# SCH.net
KiCad netlist of a schematic drawn in Altium Designer
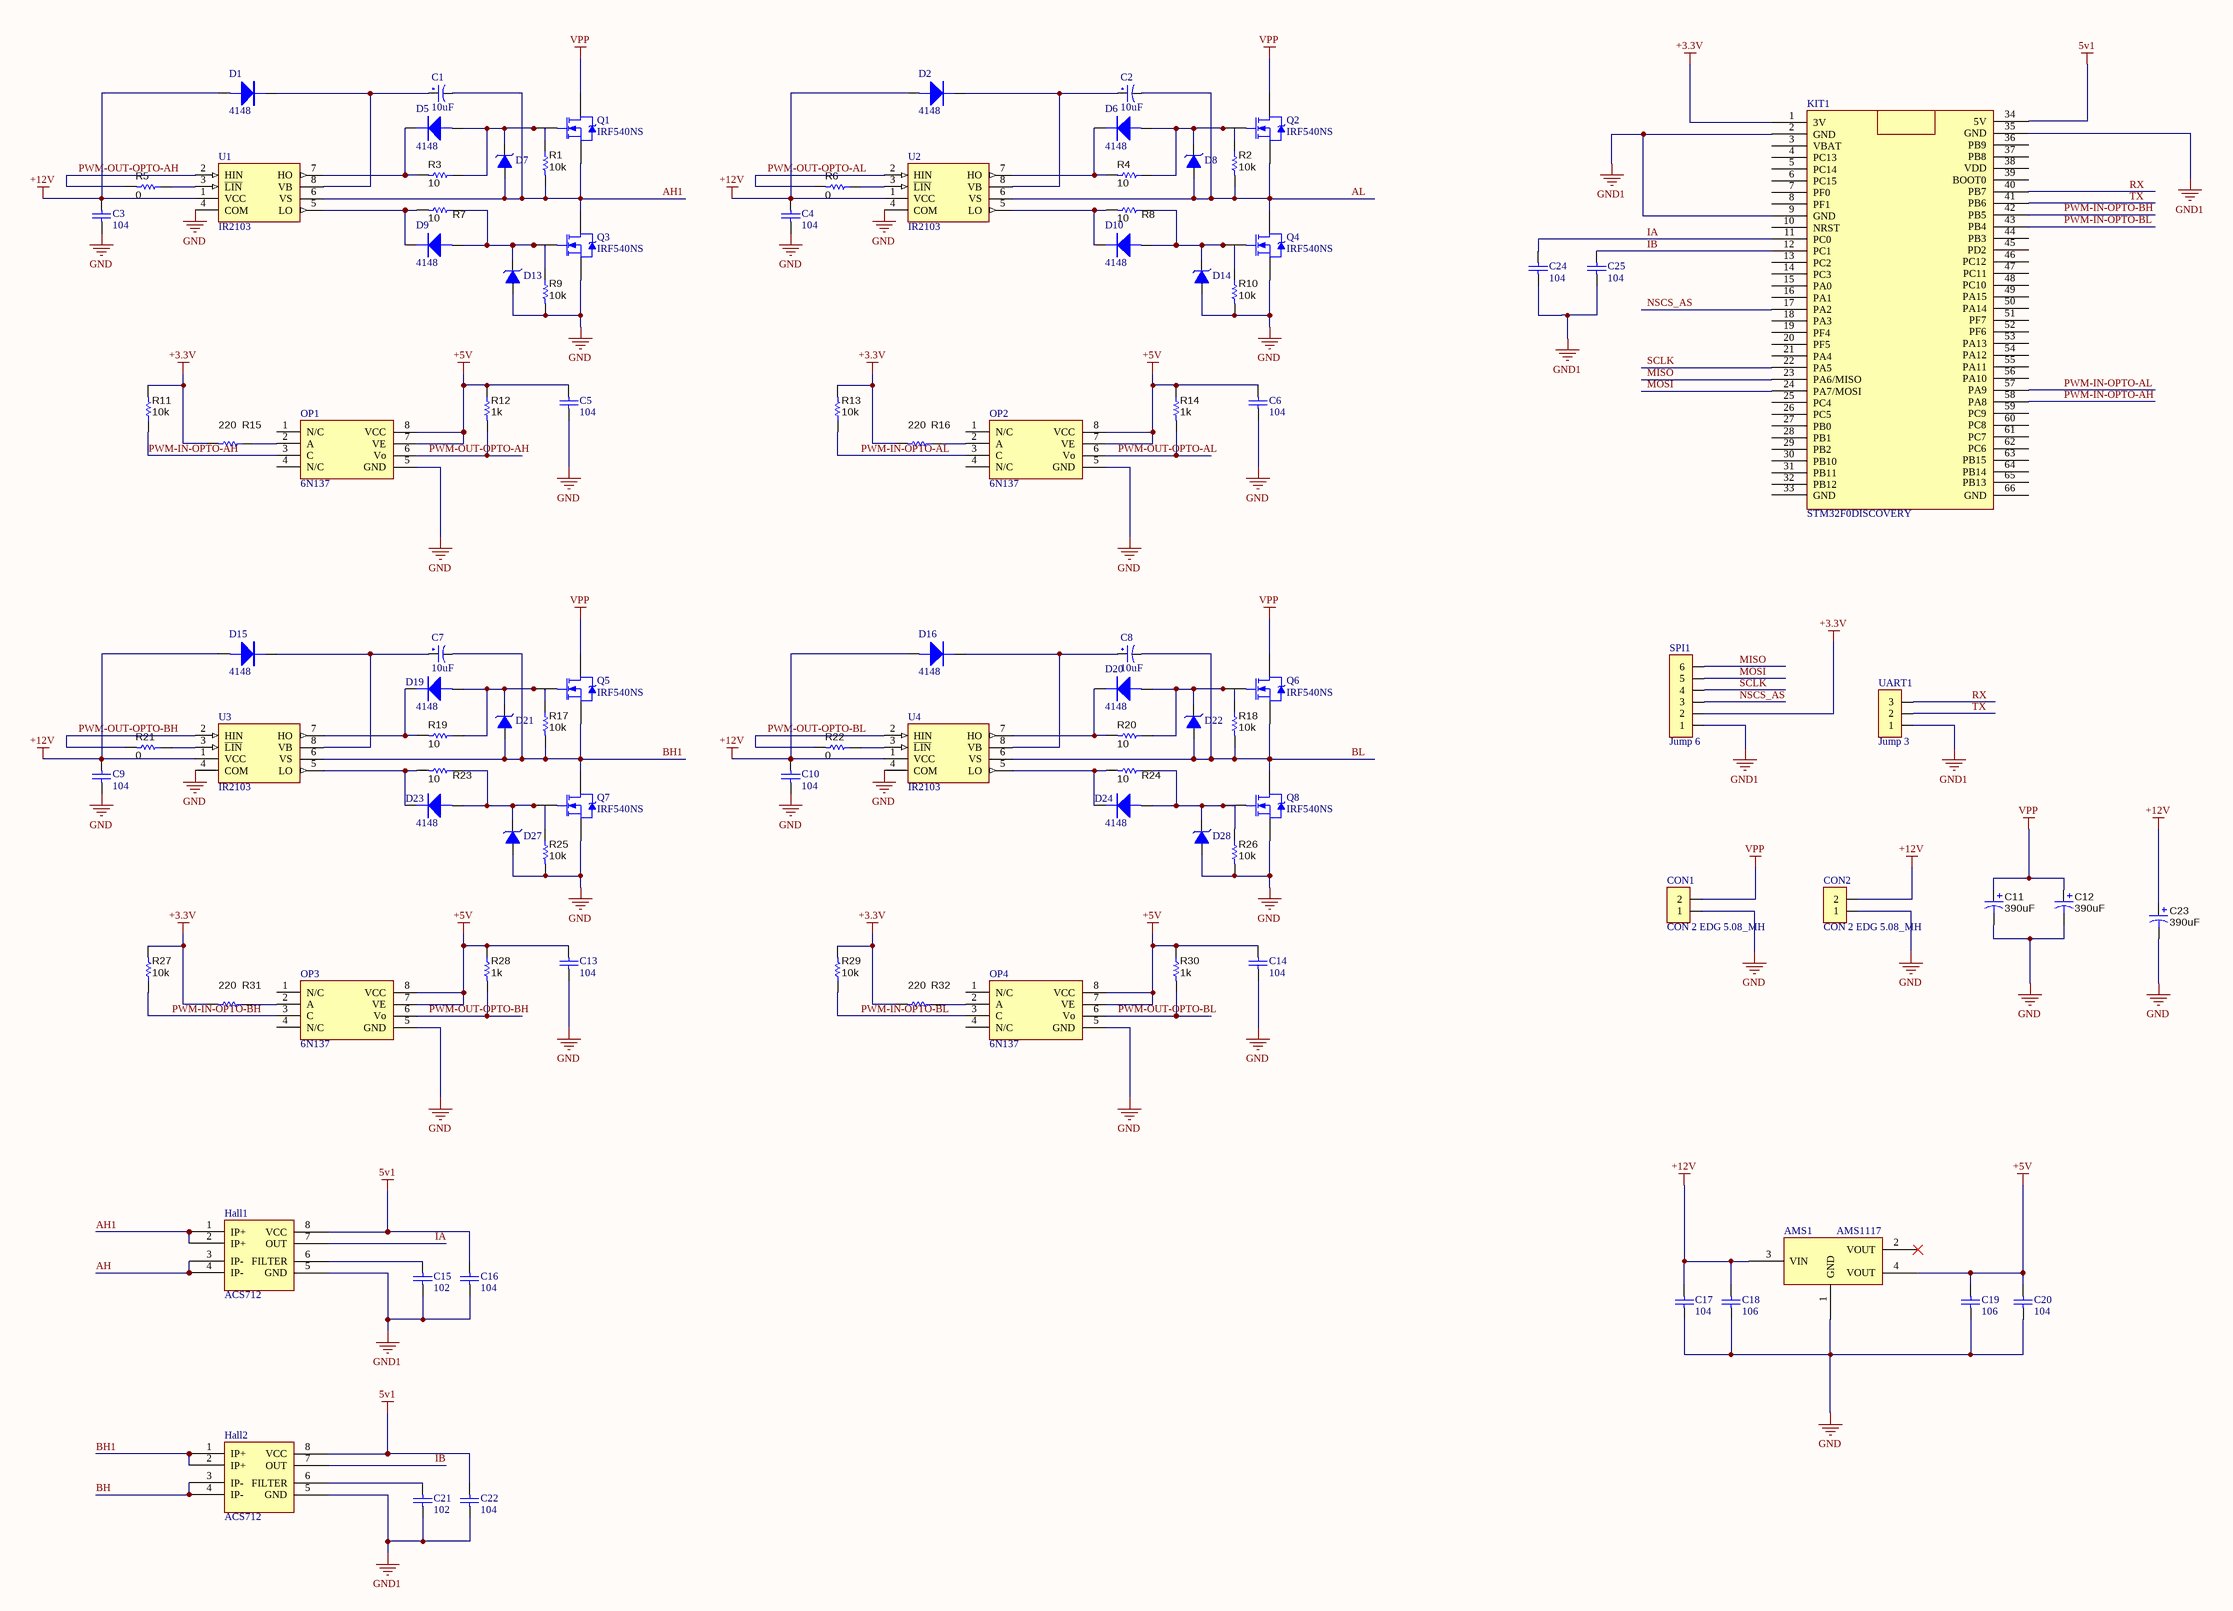
[diagram p0: SCH.SchDoc]

(export (version "E")
  (design (tool "Eeschema 10.0.6"))
  (components
    (comp (ref "AMS1")
      (value "AMS1117")
      (footprint "SOT223")
      (libsource (lib "mySch") (part "AMS1117-3.3V SOT223"))
    )
    (comp (ref "C1")
      (value "10uF")
      (footprint "CP1/2")
      (description "Cap P  0,1uF < 22uF , 16 - 50V")
      (libsource (lib "MH_DA_THU_VIEN_16122016") (part "TU_HOA_4.7uF_50V_MH"))
    )
    (comp (ref "C2")
      (value "10uF")
      (footprint "CP1/2")
      (description "Cap P  0,1uF < 22uF , 16 - 50V")
      (libsource (lib "MH_DA_THU_VIEN_16122016") (part "TU_HOA_4.7uF_50V_MH"))
    )
    (comp (ref "C3")
      (value "104")
      (footprint "TU_SMD_0805")
      (description "Ceramic Chip Capacitor - Standard")
      (fields (field (name "PUBLISHER") "Altium Limited"))
      (libsource (lib "mySch") (part "Capacitor 0805"))
    )
    (comp (ref "C4")
      (value "104")
      (footprint "TU_SMD_0805")
      (description "Ceramic Chip Capacitor - Standard")
      (fields (field (name "PUBLISHER") "Altium Limited"))
      (libsource (lib "mySch") (part "Capacitor 0805"))
    )
    (comp (ref "C5")
      (value "104")
      (footprint "TU_SMD_0805")
      (description "Ceramic Chip Capacitor - Standard")
      (fields (field (name "PUBLISHER") "Altium Limited"))
      (libsource (lib "mySch") (part "Capacitor 0805"))
    )
    (comp (ref "C6")
      (value "104")
      (footprint "TU_SMD_0805")
      (description "Ceramic Chip Capacitor - Standard")
      (fields (field (name "PUBLISHER") "Altium Limited"))
      (libsource (lib "mySch") (part "Capacitor 0805"))
    )
    (comp (ref "C7")
      (value "10uF")
      (footprint "CP1/2")
      (description "Cap P  0,1uF < 22uF , 16 - 50V")
      (libsource (lib "MH_DA_THU_VIEN_16122016") (part "TU_HOA_4.7uF_50V_MH"))
    )
    (comp (ref "C8")
      (value "10uF")
      (footprint "CP1/2")
      (description "Cap P  0,1uF < 22uF , 16 - 50V")
      (libsource (lib "MH_DA_THU_VIEN_16122016") (part "TU_HOA_4.7uF_50V_MH"))
    )
    (comp (ref "C9")
      (value "104")
      (footprint "TU_SMD_0805")
      (description "Ceramic Chip Capacitor - Standard")
      (fields (field (name "PUBLISHER") "Altium Limited"))
      (libsource (lib "mySch") (part "Capacitor 0805"))
    )
    (comp (ref "C10")
      (value "104")
      (footprint "TU_SMD_0805")
      (description "Ceramic Chip Capacitor - Standard")
      (fields (field (name "PUBLISHER") "Altium Limited"))
      (libsource (lib "mySch") (part "Capacitor 0805"))
    )
    (comp (ref "C11")
      (value "390uF")
      (footprint "CAP_12.5 X 25")
      (description "CAP ALUM 390UF 20% 50V RADIAL")
      (fields
        (field (name "PARTNUMBER") "UHW1H391MPD6")
        (field (name "MANUFACTURER") "Nichicon")
        (field (name "VALUEDISPLAYED") "390uF")
        (field (name "PUBLISHER") "Texas Instruments")
      )
      (libsource (lib "mySch") (part "Capacitor TuHoa"))
    )
    (comp (ref "C12")
      (value "390uF")
      (footprint "CAP_12.5 X 25")
      (description "CAP ALUM 390UF 20% 50V RADIAL")
      (fields
        (field (name "PARTNUMBER") "UHW1H391MPD6")
        (field (name "MANUFACTURER") "Nichicon")
        (field (name "VALUEDISPLAYED") "390uF")
        (field (name "PUBLISHER") "Texas Instruments")
      )
      (libsource (lib "mySch") (part "Capacitor TuHoa"))
    )
    (comp (ref "C13")
      (value "104")
      (footprint "TU_SMD_0805")
      (description "Ceramic Chip Capacitor - Standard")
      (fields (field (name "PUBLISHER") "Altium Limited"))
      (libsource (lib "mySch") (part "Capacitor 0805"))
    )
    (comp (ref "C14")
      (value "104")
      (footprint "TU_SMD_0805")
      (description "Ceramic Chip Capacitor - Standard")
      (fields (field (name "PUBLISHER") "Altium Limited"))
      (libsource (lib "mySch") (part "Capacitor 0805"))
    )
    (comp (ref "C15")
      (value "102")
      (footprint "TU_SMD_0805")
      (description "Ceramic Chip Capacitor - Standard")
      (fields (field (name "PUBLISHER") "Altium Limited"))
      (libsource (lib "mySch") (part "Capacitor 0805"))
    )
    (comp (ref "C16")
      (value "104")
      (footprint "TU_SMD_0805")
      (description "Ceramic Chip Capacitor - Standard")
      (fields (field (name "PUBLISHER") "Altium Limited"))
      (libsource (lib "mySch") (part "Capacitor 0805"))
    )
    (comp (ref "C17")
      (value "104")
      (footprint "TU_SMD_0805")
      (description "Ceramic Chip Capacitor - Standard")
      (fields (field (name "PUBLISHER") "Altium Limited"))
      (libsource (lib "mySch") (part "Capacitor 0805"))
    )
    (comp (ref "C18")
      (value "106")
      (footprint "TU_SMD_0805")
      (description "Ceramic Chip Capacitor - Standard")
      (fields (field (name "PUBLISHER") "Altium Limited"))
      (libsource (lib "mySch") (part "Capacitor 0805"))
    )
    (comp (ref "C19")
      (value "106")
      (footprint "TU_SMD_0805")
      (description "Ceramic Chip Capacitor - Standard")
      (fields (field (name "PUBLISHER") "Altium Limited"))
      (libsource (lib "mySch") (part "Capacitor 0805"))
    )
    (comp (ref "C20")
      (value "104")
      (footprint "TU_SMD_0805")
      (description "Ceramic Chip Capacitor - Standard")
      (fields (field (name "PUBLISHER") "Altium Limited"))
      (libsource (lib "mySch") (part "Capacitor 0805"))
    )
    (comp (ref "C21")
      (value "102")
      (footprint "TU_SMD_0805")
      (description "Ceramic Chip Capacitor - Standard")
      (fields (field (name "PUBLISHER") "Altium Limited"))
      (libsource (lib "mySch") (part "Capacitor 0805"))
    )
    (comp (ref "C22")
      (value "104")
      (footprint "TU_SMD_0805")
      (description "Ceramic Chip Capacitor - Standard")
      (fields (field (name "PUBLISHER") "Altium Limited"))
      (libsource (lib "mySch") (part "Capacitor 0805"))
    )
    (comp (ref "C23")
      (value "390uF")
      (footprint "CP1/3.0")
      (fields
        (field (name "PARTNUMBER") "UHW1H391MPD6")
        (field (name "MANUFACTURER") "Nichicon")
        (field (name "VALUEDISPLAYED") "390uF")
        (field (name "PUBLISHER") "Texas Instruments")
      )
      (libsource (lib "mySch") (part "Capacitor TuHoa"))
    )
    (comp (ref "C24")
      (value "104")
      (footprint "TU_SMD_0805")
      (description "Ceramic Chip Capacitor - Standard")
      (fields (field (name "PUBLISHER") "Altium Limited"))
      (libsource (lib "mySch") (part "Capacitor 0805"))
    )
    (comp (ref "C25")
      (value "104")
      (footprint "TU_SMD_0805")
      (description "Ceramic Chip Capacitor - Standard")
      (fields (field (name "PUBLISHER") "Altium Limited"))
      (libsource (lib "mySch") (part "Capacitor 0805"))
    )
    (comp (ref "CON1")
      (value "CON 2 EDG 5.08_MH")
      (footprint "CON 2 EDG 5.08")
      (description "CON 2 EDG 5.08 (xanh cong)")
      (libsource (lib "mySch") (part "CON 2 EDG 5.08_MH"))
    )
    (comp (ref "CON2")
      (value "CON 2 EDG 5.08_MH")
      (footprint "CON 2 EDG 5.08")
      (description "CON 2 EDG 5.08 (xanh cong)")
      (libsource (lib "mySch") (part "CON 2 EDG 5.08_MH"))
    )
    (comp (ref "D1")
      (value "4148")
      (footprint "Diode Zener 1N5363B 5W 30V")
      (description "Diode 1N4148 DO35 450mA 100V ( 1N4148 DIP)")
      (libsource (lib "MH_DA_THU_VIEN_16122016") (part "Diode 1N4148 DO35 450mA 100V ( 1N4148 DIP)_MH"))
    )
    (comp (ref "D2")
      (value "4148")
      (footprint "Diode Zener 1N5363B 5W 30V")
      (description "Diode 1N4148 DO35 450mA 100V ( 1N4148 DIP)")
      (libsource (lib "MH_DA_THU_VIEN_16122016") (part "Diode 1N4148 DO35 450mA 100V ( 1N4148 DIP)_MH"))
    )
    (comp (ref "D5")
      (value "4148")
      (footprint "Diode Zener 1N5363B 5W 30V")
      (description "Diode 1N4148 DO35 450mA 100V ( 1N4148 DIP)")
      (libsource (lib "MH_DA_THU_VIEN_16122016") (part "Diode 1N4148 DO35 450mA 100V ( 1N4148 DIP)_MH"))
    )
    (comp (ref "D6")
      (value "4148")
      (footprint "Diode Zener 1N5363B 5W 30V")
      (description "Diode 1N4148 DO35 450mA 100V ( 1N4148 DIP)")
      (libsource (lib "MH_DA_THU_VIEN_16122016") (part "Diode 1N4148 DO35 450mA 100V ( 1N4148 DIP)_MH"))
    )
    (comp (ref "D7") (value "~") (footprint "DO-35") (libsource (lib "mySch") (part "Diode Zener")))
    (comp (ref "D8") (value "~") (footprint "DO-35") (libsource (lib "mySch") (part "Diode Zener")))
    (comp (ref "D9")
      (value "4148")
      (footprint "Diode Zener 1N5363B 5W 30V")
      (description "Diode 1N4148 DO35 450mA 100V ( 1N4148 DIP)")
      (libsource (lib "MH_DA_THU_VIEN_16122016") (part "Diode 1N4148 DO35 450mA 100V ( 1N4148 DIP)_MH"))
    )
    (comp (ref "D10")
      (value "4148")
      (footprint "Diode Zener 1N5363B 5W 30V")
      (description "Diode 1N4148 DO35 450mA 100V ( 1N4148 DIP)")
      (libsource (lib "MH_DA_THU_VIEN_16122016") (part "Diode 1N4148 DO35 450mA 100V ( 1N4148 DIP)_MH"))
    )
    (comp (ref "D13") (value "~") (footprint "DO-35") (libsource (lib "mySch") (part "Diode Zener")))
    (comp (ref "D14") (value "~") (footprint "DO-35") (libsource (lib "mySch") (part "Diode Zener")))
    (comp (ref "D15")
      (value "4148")
      (footprint "Diode Zener 1N5363B 5W 30V")
      (description "Diode 1N4148 DO35 450mA 100V ( 1N4148 DIP)")
      (libsource (lib "MH_DA_THU_VIEN_16122016") (part "Diode 1N4148 DO35 450mA 100V ( 1N4148 DIP)_MH"))
    )
    (comp (ref "D16")
      (value "4148")
      (footprint "Diode Zener 1N5363B 5W 30V")
      (description "Diode 1N4148 DO35 450mA 100V ( 1N4148 DIP)")
      (libsource (lib "MH_DA_THU_VIEN_16122016") (part "Diode 1N4148 DO35 450mA 100V ( 1N4148 DIP)_MH"))
    )
    (comp (ref "D19")
      (value "4148")
      (footprint "Diode Zener 1N5363B 5W 30V")
      (description "Diode 1N4148 DO35 450mA 100V ( 1N4148 DIP)")
      (libsource (lib "MH_DA_THU_VIEN_16122016") (part "Diode 1N4148 DO35 450mA 100V ( 1N4148 DIP)_MH"))
    )
    (comp (ref "D20")
      (value "4148")
      (footprint "Diode Zener 1N5363B 5W 30V")
      (description "Diode 1N4148 DO35 450mA 100V ( 1N4148 DIP)")
      (libsource (lib "MH_DA_THU_VIEN_16122016") (part "Diode 1N4148 DO35 450mA 100V ( 1N4148 DIP)_MH"))
    )
    (comp (ref "D21") (value "~") (footprint "DO-35") (libsource (lib "mySch") (part "Diode Zener")))
    (comp (ref "D22") (value "~") (footprint "DO-35") (libsource (lib "mySch") (part "Diode Zener")))
    (comp (ref "D23")
      (value "4148")
      (footprint "Diode Zener 1N5363B 5W 30V")
      (description "Diode 1N4148 DO35 450mA 100V ( 1N4148 DIP)")
      (libsource (lib "MH_DA_THU_VIEN_16122016") (part "Diode 1N4148 DO35 450mA 100V ( 1N4148 DIP)_MH"))
    )
    (comp (ref "D24")
      (value "4148")
      (footprint "Diode Zener 1N5363B 5W 30V")
      (description "Diode 1N4148 DO35 450mA 100V ( 1N4148 DIP)")
      (libsource (lib "MH_DA_THU_VIEN_16122016") (part "Diode 1N4148 DO35 450mA 100V ( 1N4148 DIP)_MH"))
    )
    (comp (ref "D27") (value "~") (footprint "DO-35") (libsource (lib "mySch") (part "Diode Zener")))
    (comp (ref "D28") (value "~") (footprint "DO-35") (libsource (lib "mySch") (part "Diode Zener")))
    (comp (ref "Hall1") (value "ACS712") (footprint "SOP 8") (libsource (lib "mySch") (part "ACS712")))
    (comp (ref "Hall2") (value "ACS712") (footprint "SOP 8") (libsource (lib "mySch") (part "ACS712")))
    (comp (ref "KIT1")
      (value "STM32F0DISCOVERY")
      (footprint "STM32F0DISCOVERY-6N137")
      (libsource (lib "mySch") (part "STM32F0DISCOVERY"))
    )
    (comp (ref "OP1")
      (value "6N137 DIP8 Opto 10Mbit")
      (footprint "DIP8")
      (description "6N137 DIP8 Opto 10Mbit/s")
      (libsource (lib "mySch") (part "6N137"))
    )
    (comp (ref "OP2")
      (value "6N137 DIP8 Opto 10Mbit")
      (footprint "DIP8")
      (description "6N137 DIP8 Opto 10Mbit/s")
      (libsource (lib "mySch") (part "6N137"))
    )
    (comp (ref "OP3")
      (value "6N137 DIP8 Opto 10Mbit")
      (footprint "DIP8")
      (description "6N137 DIP8 Opto 10Mbit/s")
      (libsource (lib "mySch") (part "6N137"))
    )
    (comp (ref "OP4")
      (value "6N137 DIP8 Opto 10Mbit")
      (footprint "DIP8")
      (description "6N137 DIP8 Opto 10Mbit/s")
      (libsource (lib "mySch") (part "6N137"))
    )
    (comp (ref "Q1")
      (value "IRF540NS")
      (footprint "D2PAK_M_1")
      (description "HEXFET Power MOSFET")
      (fields (field (name "PUBLISHER") "Altium Limited"))
      (libsource (lib "mySch") (part "IRF540NS"))
    )
    (comp (ref "Q2")
      (value "IRF540NS")
      (footprint "D2PAK_M_1")
      (description "HEXFET Power MOSFET")
      (fields (field (name "PUBLISHER") "Altium Limited"))
      (libsource (lib "mySch") (part "IRF540NS"))
    )
    (comp (ref "Q3")
      (value "IRF540NS")
      (footprint "D2PAK_M_1")
      (description "HEXFET Power MOSFET")
      (fields (field (name "PUBLISHER") "Altium Limited"))
      (libsource (lib "mySch") (part "IRF540NS"))
    )
    (comp (ref "Q4")
      (value "IRF540NS")
      (footprint "D2PAK_M_1")
      (description "HEXFET Power MOSFET")
      (fields (field (name "PUBLISHER") "Altium Limited"))
      (libsource (lib "mySch") (part "IRF540NS"))
    )
    (comp (ref "Q5")
      (value "IRF540NS")
      (footprint "D2PAK_M_1")
      (description "HEXFET Power MOSFET")
      (fields (field (name "PUBLISHER") "Altium Limited"))
      (libsource (lib "mySch") (part "IRF540NS"))
    )
    (comp (ref "Q6")
      (value "IRF540NS")
      (footprint "D2PAK_M_1")
      (description "HEXFET Power MOSFET")
      (fields (field (name "PUBLISHER") "Altium Limited"))
      (libsource (lib "mySch") (part "IRF540NS"))
    )
    (comp (ref "Q7")
      (value "IRF540NS")
      (footprint "D2PAK_M_1")
      (description "HEXFET Power MOSFET")
      (fields (field (name "PUBLISHER") "Altium Limited"))
      (libsource (lib "mySch") (part "IRF540NS"))
    )
    (comp (ref "Q8")
      (value "IRF540NS")
      (footprint "D2PAK_M_1")
      (description "HEXFET Power MOSFET")
      (fields (field (name "PUBLISHER") "Altium Limited"))
      (libsource (lib "mySch") (part "IRF540NS"))
    )
    (comp (ref "R1")
      (value "10k")
      (footprint "Tro SMD 0805")
      (description "RES, 100, 1%, 0.1 W, 0402")
      (fields
        (field (name "PARTNUMBER") "ERJ-2RKF1000X")
        (field (name "MANUFACTURER") "Panasonic")
        (field (name "PUBLISHER") "Texas Instruments")
      )
      (libsource (lib "mySch") (part "R nho"))
    )
    (comp (ref "R2")
      (value "10k")
      (footprint "Tro SMD 0805")
      (description "RES, 100, 1%, 0.1 W, 0402")
      (fields
        (field (name "PARTNUMBER") "ERJ-2RKF1000X")
        (field (name "MANUFACTURER") "Panasonic")
        (field (name "PUBLISHER") "Texas Instruments")
      )
      (libsource (lib "mySch") (part "R nho"))
    )
    (comp (ref "R3")
      (value "10")
      (footprint "Tro SMD 0805")
      (description "RES, 100, 1%, 0.1 W, 0402")
      (fields
        (field (name "PARTNUMBER") "ERJ-2RKF1000X")
        (field (name "MANUFACTURER") "Panasonic")
        (field (name "PUBLISHER") "Texas Instruments")
      )
      (libsource (lib "mySch") (part "R nho"))
    )
    (comp (ref "R4")
      (value "10")
      (footprint "Tro SMD 0805")
      (description "RES, 100, 1%, 0.1 W, 0402")
      (fields
        (field (name "PARTNUMBER") "ERJ-2RKF1000X")
        (field (name "MANUFACTURER") "Panasonic")
        (field (name "PUBLISHER") "Texas Instruments")
      )
      (libsource (lib "mySch") (part "R nho"))
    )
    (comp (ref "R5")
      (value "0")
      (footprint "Tro SMD 0805")
      (description "RES, 100, 1%, 0.1 W, 0402")
      (fields
        (field (name "PARTNUMBER") "ERJ-2RKF1000X")
        (field (name "MANUFACTURER") "Panasonic")
        (field (name "PUBLISHER") "Texas Instruments")
      )
      (libsource (lib "mySch") (part "R nho"))
    )
    (comp (ref "R6")
      (value "0")
      (footprint "Tro SMD 0805")
      (description "RES, 100, 1%, 0.1 W, 0402")
      (fields
        (field (name "PARTNUMBER") "ERJ-2RKF1000X")
        (field (name "MANUFACTURER") "Panasonic")
        (field (name "PUBLISHER") "Texas Instruments")
      )
      (libsource (lib "mySch") (part "R nho"))
    )
    (comp (ref "R7")
      (value "10")
      (footprint "Tro SMD 0805")
      (description "RES, 100, 1%, 0.1 W, 0402")
      (fields
        (field (name "PARTNUMBER") "ERJ-2RKF1000X")
        (field (name "MANUFACTURER") "Panasonic")
        (field (name "PUBLISHER") "Texas Instruments")
      )
      (libsource (lib "mySch") (part "R nho"))
    )
    (comp (ref "R8")
      (value "10")
      (footprint "Tro SMD 0805")
      (description "RES, 100, 1%, 0.1 W, 0402")
      (fields
        (field (name "PARTNUMBER") "ERJ-2RKF1000X")
        (field (name "MANUFACTURER") "Panasonic")
        (field (name "PUBLISHER") "Texas Instruments")
      )
      (libsource (lib "mySch") (part "R nho"))
    )
    (comp (ref "R9")
      (value "10k")
      (footprint "Tro SMD 0805")
      (description "RES, 100, 1%, 0.1 W, 0402")
      (fields
        (field (name "PARTNUMBER") "ERJ-2RKF1000X")
        (field (name "MANUFACTURER") "Panasonic")
        (field (name "PUBLISHER") "Texas Instruments")
      )
      (libsource (lib "mySch") (part "R nho"))
    )
    (comp (ref "R10")
      (value "10k")
      (footprint "Tro SMD 0805")
      (description "RES, 100, 1%, 0.1 W, 0402")
      (fields
        (field (name "PARTNUMBER") "ERJ-2RKF1000X")
        (field (name "MANUFACTURER") "Panasonic")
        (field (name "PUBLISHER") "Texas Instruments")
      )
      (libsource (lib "mySch") (part "R nho"))
    )
    (comp (ref "R11")
      (value "10k")
      (footprint "Tro SMD 0805")
      (description "RES, 100, 1%, 0.1 W, 0402")
      (fields
        (field (name "PARTNUMBER") "ERJ-2RKF1000X")
        (field (name "MANUFACTURER") "Panasonic")
        (field (name "PUBLISHER") "Texas Instruments")
      )
      (libsource (lib "mySch") (part "R nho"))
    )
    (comp (ref "R12")
      (value "1k")
      (footprint "Tro SMD 0805")
      (description "RES, 100, 1%, 0.1 W, 0402")
      (fields
        (field (name "PARTNUMBER") "ERJ-2RKF1000X")
        (field (name "MANUFACTURER") "Panasonic")
        (field (name "PUBLISHER") "Texas Instruments")
      )
      (libsource (lib "mySch") (part "R nho"))
    )
    (comp (ref "R13")
      (value "10k")
      (footprint "Tro SMD 0805")
      (description "RES, 100, 1%, 0.1 W, 0402")
      (fields
        (field (name "PARTNUMBER") "ERJ-2RKF1000X")
        (field (name "MANUFACTURER") "Panasonic")
        (field (name "PUBLISHER") "Texas Instruments")
      )
      (libsource (lib "mySch") (part "R nho"))
    )
    (comp (ref "R14")
      (value "1k")
      (footprint "Tro SMD 0805")
      (description "RES, 100, 1%, 0.1 W, 0402")
      (fields
        (field (name "PARTNUMBER") "ERJ-2RKF1000X")
        (field (name "MANUFACTURER") "Panasonic")
        (field (name "PUBLISHER") "Texas Instruments")
      )
      (libsource (lib "mySch") (part "R nho"))
    )
    (comp (ref "R15")
      (value "220")
      (footprint "Tro SMD 0805")
      (description "RES, 100, 1%, 0.1 W, 0402")
      (fields
        (field (name "PARTNUMBER") "ERJ-2RKF1000X")
        (field (name "MANUFACTURER") "Panasonic")
        (field (name "PUBLISHER") "Texas Instruments")
      )
      (libsource (lib "mySch") (part "R nho"))
    )
    (comp (ref "R16")
      (value "220")
      (footprint "Tro SMD 0805")
      (description "RES, 100, 1%, 0.1 W, 0402")
      (fields
        (field (name "PARTNUMBER") "ERJ-2RKF1000X")
        (field (name "MANUFACTURER") "Panasonic")
        (field (name "PUBLISHER") "Texas Instruments")
      )
      (libsource (lib "mySch") (part "R nho"))
    )
    (comp (ref "R17")
      (value "10k")
      (footprint "Tro SMD 0805")
      (description "RES, 100, 1%, 0.1 W, 0402")
      (fields
        (field (name "PARTNUMBER") "ERJ-2RKF1000X")
        (field (name "MANUFACTURER") "Panasonic")
        (field (name "PUBLISHER") "Texas Instruments")
      )
      (libsource (lib "mySch") (part "R nho"))
    )
    (comp (ref "R18")
      (value "10k")
      (footprint "Tro SMD 0805")
      (description "RES, 100, 1%, 0.1 W, 0402")
      (fields
        (field (name "PARTNUMBER") "ERJ-2RKF1000X")
        (field (name "MANUFACTURER") "Panasonic")
        (field (name "PUBLISHER") "Texas Instruments")
      )
      (libsource (lib "mySch") (part "R nho"))
    )
    (comp (ref "R19")
      (value "10")
      (footprint "Tro SMD 0805")
      (description "RES, 100, 1%, 0.1 W, 0402")
      (fields
        (field (name "PARTNUMBER") "ERJ-2RKF1000X")
        (field (name "MANUFACTURER") "Panasonic")
        (field (name "PUBLISHER") "Texas Instruments")
      )
      (libsource (lib "mySch") (part "R nho"))
    )
    (comp (ref "R20")
      (value "10")
      (footprint "Tro SMD 0805")
      (description "RES, 100, 1%, 0.1 W, 0402")
      (fields
        (field (name "PARTNUMBER") "ERJ-2RKF1000X")
        (field (name "MANUFACTURER") "Panasonic")
        (field (name "PUBLISHER") "Texas Instruments")
      )
      (libsource (lib "mySch") (part "R nho"))
    )
    (comp (ref "R21")
      (value "0")
      (footprint "Tro SMD 0805")
      (description "RES, 100, 1%, 0.1 W, 0402")
      (fields
        (field (name "PARTNUMBER") "ERJ-2RKF1000X")
        (field (name "MANUFACTURER") "Panasonic")
        (field (name "PUBLISHER") "Texas Instruments")
      )
      (libsource (lib "mySch") (part "R nho"))
    )
    (comp (ref "R22")
      (value "0")
      (footprint "Tro SMD 0805")
      (description "RES, 100, 1%, 0.1 W, 0402")
      (fields
        (field (name "PARTNUMBER") "ERJ-2RKF1000X")
        (field (name "MANUFACTURER") "Panasonic")
        (field (name "PUBLISHER") "Texas Instruments")
      )
      (libsource (lib "mySch") (part "R nho"))
    )
    (comp (ref "R23")
      (value "10")
      (footprint "Tro SMD 0805")
      (description "RES, 100, 1%, 0.1 W, 0402")
      (fields
        (field (name "PARTNUMBER") "ERJ-2RKF1000X")
        (field (name "MANUFACTURER") "Panasonic")
        (field (name "PUBLISHER") "Texas Instruments")
      )
      (libsource (lib "mySch") (part "R nho"))
    )
    (comp (ref "R24")
      (value "10")
      (footprint "Tro SMD 0805")
      (description "RES, 100, 1%, 0.1 W, 0402")
      (fields
        (field (name "PARTNUMBER") "ERJ-2RKF1000X")
        (field (name "MANUFACTURER") "Panasonic")
        (field (name "PUBLISHER") "Texas Instruments")
      )
      (libsource (lib "mySch") (part "R nho"))
    )
    (comp (ref "R25")
      (value "10k")
      (footprint "Tro SMD 0805")
      (description "RES, 100, 1%, 0.1 W, 0402")
      (fields
        (field (name "PARTNUMBER") "ERJ-2RKF1000X")
        (field (name "MANUFACTURER") "Panasonic")
        (field (name "PUBLISHER") "Texas Instruments")
      )
      (libsource (lib "mySch") (part "R nho"))
    )
    (comp (ref "R26")
      (value "10k")
      (footprint "Tro SMD 0805")
      (description "RES, 100, 1%, 0.1 W, 0402")
      (fields
        (field (name "PARTNUMBER") "ERJ-2RKF1000X")
        (field (name "MANUFACTURER") "Panasonic")
        (field (name "PUBLISHER") "Texas Instruments")
      )
      (libsource (lib "mySch") (part "R nho"))
    )
    (comp (ref "R27")
      (value "10k")
      (footprint "Tro SMD 0805")
      (description "RES, 100, 1%, 0.1 W, 0402")
      (fields
        (field (name "PARTNUMBER") "ERJ-2RKF1000X")
        (field (name "MANUFACTURER") "Panasonic")
        (field (name "PUBLISHER") "Texas Instruments")
      )
      (libsource (lib "mySch") (part "R nho"))
    )
    (comp (ref "R28")
      (value "1k")
      (footprint "Tro SMD 0805")
      (description "RES, 100, 1%, 0.1 W, 0402")
      (fields
        (field (name "PARTNUMBER") "ERJ-2RKF1000X")
        (field (name "MANUFACTURER") "Panasonic")
        (field (name "PUBLISHER") "Texas Instruments")
      )
      (libsource (lib "mySch") (part "R nho"))
    )
    (comp (ref "R29")
      (value "10k")
      (footprint "Tro SMD 0805")
      (description "RES, 100, 1%, 0.1 W, 0402")
      (fields
        (field (name "PARTNUMBER") "ERJ-2RKF1000X")
        (field (name "MANUFACTURER") "Panasonic")
        (field (name "PUBLISHER") "Texas Instruments")
      )
      (libsource (lib "mySch") (part "R nho"))
    )
    (comp (ref "R30")
      (value "1k")
      (footprint "Tro SMD 0805")
      (description "RES, 100, 1%, 0.1 W, 0402")
      (fields
        (field (name "PARTNUMBER") "ERJ-2RKF1000X")
        (field (name "MANUFACTURER") "Panasonic")
        (field (name "PUBLISHER") "Texas Instruments")
      )
      (libsource (lib "mySch") (part "R nho"))
    )
    (comp (ref "R31")
      (value "220")
      (footprint "Tro SMD 0805")
      (description "RES, 100, 1%, 0.1 W, 0402")
      (fields
        (field (name "PARTNUMBER") "ERJ-2RKF1000X")
        (field (name "MANUFACTURER") "Panasonic")
        (field (name "PUBLISHER") "Texas Instruments")
      )
      (libsource (lib "mySch") (part "R nho"))
    )
    (comp (ref "R32")
      (value "220")
      (footprint "Tro SMD 0805")
      (description "RES, 100, 1%, 0.1 W, 0402")
      (fields
        (field (name "PARTNUMBER") "ERJ-2RKF1000X")
        (field (name "MANUFACTURER") "Panasonic")
        (field (name "PUBLISHER") "Texas Instruments")
      )
      (libsource (lib "mySch") (part "R nho"))
    )
    (comp (ref "SPI1")
      (value "Jump 6")
      (footprint "ZH 1.5 6P")
      (description "Jump 6P 2.54")
      (libsource (lib "mySch") (part "Jump 6"))
    )
    (comp (ref "U1")
      (value "IR2103")
      (footprint "SOP 8")
      (description "High and Low Side Driver")
      (fields (field (name "PUBLISHER") "Altium Limited"))
      (libsource (lib "IR Interface Bridge Driver") (part "IR2103"))
    )
    (comp (ref "U2")
      (value "IR2103")
      (footprint "SOP 8")
      (description "High and Low Side Driver")
      (fields (field (name "PUBLISHER") "Altium Limited"))
      (libsource (lib "IR Interface Bridge Driver") (part "IR2103"))
    )
    (comp (ref "U3")
      (value "IR2103")
      (footprint "SOP 8")
      (description "High and Low Side Driver")
      (fields (field (name "PUBLISHER") "Altium Limited"))
      (libsource (lib "IR Interface Bridge Driver") (part "IR2103"))
    )
    (comp (ref "U4")
      (value "IR2103")
      (footprint "SOP 8")
      (description "High and Low Side Driver")
      (fields (field (name "PUBLISHER") "Altium Limited"))
      (libsource (lib "IR Interface Bridge Driver") (part "IR2103"))
    )
    (comp (ref "UART1")
      (value "Jump 3")
      (footprint "Jump 3")
      (description "Jump 3P 2.54")
      (libsource (lib "mySch") (part "Jump 3"))
    )
  )
  (nets
    (net (code "1") (name "+3.3V") (class "Default")
      (node (ref "KIT1") (pin "1") (pinfunction "3V_1") (pintype "passive"))
      (node (ref "R11") (pin "2") (pinfunction "2_2") (pintype "passive"))
      (node (ref "R13") (pin "2") (pinfunction "2_2") (pintype "passive"))
      (node (ref "R15") (pin "2") (pinfunction "2_2") (pintype "passive"))
      (node (ref "R16") (pin "2") (pinfunction "2_2") (pintype "passive"))
      (node (ref "R27") (pin "2") (pinfunction "2_2") (pintype "passive"))
      (node (ref "R29") (pin "2") (pinfunction "2_2") (pintype "passive"))
      (node (ref "R31") (pin "2") (pinfunction "2_2") (pintype "passive"))
      (node (ref "R32") (pin "2") (pinfunction "2_2") (pintype "passive"))
      (node (ref "SPI1") (pin "2") (pinfunction "2_2") (pintype "passive"))
    )
    (net (code "2") (name "+5V") (class "Default")
      (node (ref "AMS1") (pin "4") (pinfunction "VOUT_4") (pintype "passive"))
      (node (ref "C13") (pin "2") (pinfunction "2_2") (pintype "passive"))
      (node (ref "C14") (pin "2") (pinfunction "2_2") (pintype "passive"))
      (node (ref "C19") (pin "2") (pinfunction "2_2") (pintype "passive"))
      (node (ref "C20") (pin "2") (pinfunction "2_2") (pintype "passive"))
      (node (ref "C5") (pin "2") (pinfunction "2_2") (pintype "passive"))
      (node (ref "C6") (pin "2") (pinfunction "2_2") (pintype "passive"))
      (node (ref "OP1") (pin "7") (pinfunction "VE_7") (pintype "passive"))
      (node (ref "OP1") (pin "8") (pinfunction "VCC_8") (pintype "passive"))
      (node (ref "OP2") (pin "7") (pinfunction "VE_7") (pintype "passive"))
      (node (ref "OP2") (pin "8") (pinfunction "VCC_8") (pintype "passive"))
      (node (ref "OP3") (pin "7") (pinfunction "VE_7") (pintype "passive"))
      (node (ref "OP3") (pin "8") (pinfunction "VCC_8") (pintype "passive"))
      (node (ref "OP4") (pin "7") (pinfunction "VE_7") (pintype "passive"))
      (node (ref "OP4") (pin "8") (pinfunction "VCC_8") (pintype "passive"))
      (node (ref "R12") (pin "1") (pinfunction "1_1") (pintype "passive"))
      (node (ref "R14") (pin "1") (pinfunction "1_1") (pintype "passive"))
      (node (ref "R28") (pin "1") (pinfunction "1_1") (pintype "passive"))
      (node (ref "R30") (pin "1") (pinfunction "1_1") (pintype "passive"))
    )
    (net (code "3") (name "+12V") (class "Default")
      (node (ref "AMS1") (pin "3") (pinfunction "VIN_3") (pintype "passive"))
      (node (ref "C10") (pin "2") (pinfunction "2_2") (pintype "passive"))
      (node (ref "C17") (pin "2") (pinfunction "2_2") (pintype "passive"))
      (node (ref "C18") (pin "2") (pinfunction "2_2") (pintype "passive"))
      (node (ref "C23") (pin "1") (pinfunction "+_1") (pintype "passive"))
      (node (ref "C3") (pin "2") (pinfunction "2_2") (pintype "passive"))
      (node (ref "C4") (pin "2") (pinfunction "2_2") (pintype "passive"))
      (node (ref "C9") (pin "2") (pinfunction "2_2") (pintype "passive"))
      (node (ref "CON2") (pin "2") (pinfunction "2_2") (pintype "passive"))
      (node (ref "D1") (pin "1") (pinfunction "1_1") (pintype "passive"))
      (node (ref "D15") (pin "1") (pinfunction "1_1") (pintype "passive"))
      (node (ref "D16") (pin "1") (pinfunction "1_1") (pintype "passive"))
      (node (ref "D2") (pin "1") (pinfunction "1_1") (pintype "passive"))
      (node (ref "U1") (pin "1") (pinfunction "VCC_1") (pintype "power_in"))
      (node (ref "U2") (pin "1") (pinfunction "VCC_1") (pintype "power_in"))
      (node (ref "U3") (pin "1") (pinfunction "VCC_1") (pintype "power_in"))
      (node (ref "U4") (pin "1") (pinfunction "VCC_1") (pintype "power_in"))
    )
    (net (code "4") (name "/AH") (class "Default")
      (node (ref "Hall1") (pin "3") (pinfunction "IP-_3") (pintype "passive"))
      (node (ref "Hall1") (pin "4") (pinfunction "IP-_4") (pintype "passive"))
    )
    (net (code "5") (name "/AH1") (class "Default")
      (node (ref "C1") (pin "2") (pinfunction "2_2") (pintype "passive"))
      (node (ref "D7") (pin "1") (pinfunction "A_1") (pintype "passive"))
      (node (ref "Hall1") (pin "1") (pinfunction "IP+_1") (pintype "passive"))
      (node (ref "Hall1") (pin "2") (pinfunction "IP+_2") (pintype "passive"))
      (node (ref "Q1") (pin "3") (pinfunction "S_3") (pintype "passive"))
      (node (ref "Q3") (pin "2") (pinfunction "D_2") (pintype "passive"))
      (node (ref "R1") (pin "2") (pinfunction "2_2") (pintype "passive"))
      (node (ref "U1") (pin "6") (pinfunction "VS_6") (pintype "power_in"))
    )
    (net (code "6") (name "/AL") (class "Default")
      (node (ref "C2") (pin "2") (pinfunction "2_2") (pintype "passive"))
      (node (ref "D8") (pin "1") (pinfunction "A_1") (pintype "passive"))
      (node (ref "Q2") (pin "3") (pinfunction "S_3") (pintype "passive"))
      (node (ref "Q4") (pin "2") (pinfunction "D_2") (pintype "passive"))
      (node (ref "R2") (pin "2") (pinfunction "2_2") (pintype "passive"))
      (node (ref "U2") (pin "6") (pinfunction "VS_6") (pintype "power_in"))
    )
    (net (code "7") (name "/BH") (class "Default")
      (node (ref "Hall2") (pin "3") (pinfunction "IP-_3") (pintype "passive"))
      (node (ref "Hall2") (pin "4") (pinfunction "IP-_4") (pintype "passive"))
    )
    (net (code "8") (name "/BH1") (class "Default")
      (node (ref "C7") (pin "2") (pinfunction "2_2") (pintype "passive"))
      (node (ref "D21") (pin "1") (pinfunction "A_1") (pintype "passive"))
      (node (ref "Hall2") (pin "1") (pinfunction "IP+_1") (pintype "passive"))
      (node (ref "Hall2") (pin "2") (pinfunction "IP+_2") (pintype "passive"))
      (node (ref "Q5") (pin "3") (pinfunction "S_3") (pintype "passive"))
      (node (ref "Q7") (pin "2") (pinfunction "D_2") (pintype "passive"))
      (node (ref "R17") (pin "2") (pinfunction "2_2") (pintype "passive"))
      (node (ref "U3") (pin "6") (pinfunction "VS_6") (pintype "power_in"))
    )
    (net (code "9") (name "/BL") (class "Default")
      (node (ref "C8") (pin "2") (pinfunction "2_2") (pintype "passive"))
      (node (ref "D22") (pin "1") (pinfunction "A_1") (pintype "passive"))
      (node (ref "Q6") (pin "3") (pinfunction "S_3") (pintype "passive"))
      (node (ref "Q8") (pin "2") (pinfunction "D_2") (pintype "passive"))
      (node (ref "R18") (pin "2") (pinfunction "2_2") (pintype "passive"))
      (node (ref "U4") (pin "6") (pinfunction "VS_6") (pintype "power_in"))
    )
    (net (code "10") (name "/IA") (class "Default")
      (node (ref "C24") (pin "2") (pinfunction "2_2") (pintype "passive"))
      (node (ref "Hall1") (pin "7") (pinfunction "OUT_7") (pintype "passive"))
      (node (ref "KIT1") (pin "11") (pinfunction "PC0_11") (pintype "passive"))
    )
    (net (code "11") (name "/IB") (class "Default")
      (node (ref "C25") (pin "2") (pinfunction "2_2") (pintype "passive"))
      (node (ref "Hall2") (pin "7") (pinfunction "OUT_7") (pintype "passive"))
      (node (ref "KIT1") (pin "12") (pinfunction "PC1_12") (pintype "passive"))
    )
    (net (code "12") (name "/MISO") (class "Default")
      (node (ref "KIT1") (pin "23") (pinfunction "PA6/MISO_23") (pintype "passive"))
      (node (ref "SPI1") (pin "6") (pinfunction "6_6") (pintype "passive"))
    )
    (net (code "13") (name "/MOSI") (class "Default")
      (node (ref "KIT1") (pin "24") (pinfunction "PA7/MOSI_24") (pintype "passive"))
      (node (ref "SPI1") (pin "5") (pinfunction "5_5") (pintype "passive"))
    )
    (net (code "14") (name "/NSCS_AS") (class "Default")
      (node (ref "KIT1") (pin "17") (pinfunction "PA2_17") (pintype "passive"))
      (node (ref "SPI1") (pin "3") (pinfunction "3_3") (pintype "passive"))
    )
    (net (code "15") (name "/PWM-IN-OPTO-AH") (class "Default")
      (node (ref "KIT1") (pin "58") (pinfunction "PA8_58") (pintype "passive"))
      (node (ref "OP1") (pin "3") (pinfunction "C_3") (pintype "passive"))
      (node (ref "R11") (pin "1") (pinfunction "1_1") (pintype "passive"))
    )
    (net (code "16") (name "/PWM-IN-OPTO-AL") (class "Default")
      (node (ref "KIT1") (pin "57") (pinfunction "PA9_57") (pintype "passive"))
      (node (ref "OP2") (pin "3") (pinfunction "C_3") (pintype "passive"))
      (node (ref "R13") (pin "1") (pinfunction "1_1") (pintype "passive"))
    )
    (net (code "17") (name "/PWM-IN-OPTO-BH") (class "Default")
      (node (ref "KIT1") (pin "42") (pinfunction "PB5_42") (pintype "passive"))
      (node (ref "OP3") (pin "3") (pinfunction "C_3") (pintype "passive"))
      (node (ref "R27") (pin "1") (pinfunction "1_1") (pintype "passive"))
    )
    (net (code "18") (name "/PWM-IN-OPTO-BL") (class "Default")
      (node (ref "KIT1") (pin "43") (pinfunction "PB4_43") (pintype "passive"))
      (node (ref "OP4") (pin "3") (pinfunction "C_3") (pintype "passive"))
      (node (ref "R29") (pin "1") (pinfunction "1_1") (pintype "passive"))
    )
    (net (code "19") (name "/PWM-OUT-OPTO-AH") (class "Default")
      (node (ref "OP1") (pin "6") (pinfunction "Vo_6") (pintype "passive"))
      (node (ref "R12") (pin "2") (pinfunction "2_2") (pintype "passive"))
      (node (ref "R5") (pin "2") (pinfunction "2_2") (pintype "passive"))
      (node (ref "U1") (pin "2") (pinfunction "HIN_2") (pintype "input"))
    )
    (net (code "20") (name "/PWM-OUT-OPTO-AL") (class "Default")
      (node (ref "OP2") (pin "6") (pinfunction "Vo_6") (pintype "passive"))
      (node (ref "R14") (pin "2") (pinfunction "2_2") (pintype "passive"))
      (node (ref "R6") (pin "2") (pinfunction "2_2") (pintype "passive"))
      (node (ref "U2") (pin "2") (pinfunction "HIN_2") (pintype "input"))
    )
    (net (code "21") (name "/PWM-OUT-OPTO-BH") (class "Default")
      (node (ref "OP3") (pin "6") (pinfunction "Vo_6") (pintype "passive"))
      (node (ref "R21") (pin "2") (pinfunction "2_2") (pintype "passive"))
      (node (ref "R28") (pin "2") (pinfunction "2_2") (pintype "passive"))
      (node (ref "U3") (pin "2") (pinfunction "HIN_2") (pintype "input"))
    )
    (net (code "22") (name "/PWM-OUT-OPTO-BL") (class "Default")
      (node (ref "OP4") (pin "6") (pinfunction "Vo_6") (pintype "passive"))
      (node (ref "R22") (pin "2") (pinfunction "2_2") (pintype "passive"))
      (node (ref "R30") (pin "2") (pinfunction "2_2") (pintype "passive"))
      (node (ref "U4") (pin "2") (pinfunction "HIN_2") (pintype "input"))
    )
    (net (code "23") (name "/RX") (class "Default")
      (node (ref "KIT1") (pin "40") (pinfunction "PB7_40") (pintype "passive"))
      (node (ref "UART1") (pin "3") (pinfunction "3_3") (pintype "passive"))
    )
    (net (code "24") (name "/SCLK") (class "Default")
      (node (ref "KIT1") (pin "22") (pinfunction "PA5_22") (pintype "passive"))
      (node (ref "SPI1") (pin "4") (pinfunction "4_4") (pintype "passive"))
    )
    (net (code "25") (name "/TX") (class "Default")
      (node (ref "KIT1") (pin "41") (pinfunction "PB6_41") (pintype "passive"))
      (node (ref "UART1") (pin "2") (pinfunction "2_2") (pintype "passive"))
    )
    (net (code "26") (name "5v1") (class "Default")
      (node (ref "C16") (pin "2") (pinfunction "2_2") (pintype "passive"))
      (node (ref "C22") (pin "2") (pinfunction "2_2") (pintype "passive"))
      (node (ref "Hall1") (pin "8") (pinfunction "VCC_8") (pintype "passive"))
      (node (ref "Hall2") (pin "8") (pinfunction "VCC_8") (pintype "passive"))
      (node (ref "KIT1") (pin "34") (pinfunction "5V_34") (pintype "passive"))
    )
    (net (code "27") (name "GND") (class "Default")
      (node (ref "AMS1") (pin "1") (pinfunction "GND_1") (pintype "passive"))
      (node (ref "C10") (pin "1") (pinfunction "1_1") (pintype "passive"))
      (node (ref "C11") (pin "2") (pinfunction "-_2") (pintype "passive"))
      (node (ref "C12") (pin "2") (pinfunction "-_2") (pintype "passive"))
      (node (ref "C13") (pin "1") (pinfunction "1_1") (pintype "passive"))
      (node (ref "C14") (pin "1") (pinfunction "1_1") (pintype "passive"))
      (node (ref "C17") (pin "1") (pinfunction "1_1") (pintype "passive"))
      (node (ref "C18") (pin "1") (pinfunction "1_1") (pintype "passive"))
      (node (ref "C19") (pin "1") (pinfunction "1_1") (pintype "passive"))
      (node (ref "C20") (pin "1") (pinfunction "1_1") (pintype "passive"))
      (node (ref "C23") (pin "2") (pinfunction "-_2") (pintype "passive"))
      (node (ref "C3") (pin "1") (pinfunction "1_1") (pintype "passive"))
      (node (ref "C4") (pin "1") (pinfunction "1_1") (pintype "passive"))
      (node (ref "C5") (pin "1") (pinfunction "1_1") (pintype "passive"))
      (node (ref "C6") (pin "1") (pinfunction "1_1") (pintype "passive"))
      (node (ref "C9") (pin "1") (pinfunction "1_1") (pintype "passive"))
      (node (ref "CON1") (pin "1") (pinfunction "1_1") (pintype "passive"))
      (node (ref "CON2") (pin "1") (pinfunction "1_1") (pintype "passive"))
      (node (ref "D13") (pin "1") (pinfunction "A_1") (pintype "passive"))
      (node (ref "D14") (pin "1") (pinfunction "A_1") (pintype "passive"))
      (node (ref "D27") (pin "1") (pinfunction "A_1") (pintype "passive"))
      (node (ref "D28") (pin "1") (pinfunction "A_1") (pintype "passive"))
      (node (ref "OP1") (pin "5") (pinfunction "GND_5") (pintype "passive"))
      (node (ref "OP2") (pin "5") (pinfunction "GND_5") (pintype "passive"))
      (node (ref "OP3") (pin "5") (pinfunction "GND_5") (pintype "passive"))
      (node (ref "OP4") (pin "5") (pinfunction "GND_5") (pintype "passive"))
      (node (ref "Q3") (pin "3") (pinfunction "S_3") (pintype "passive"))
      (node (ref "Q4") (pin "3") (pinfunction "S_3") (pintype "passive"))
      (node (ref "Q7") (pin "3") (pinfunction "S_3") (pintype "passive"))
      (node (ref "Q8") (pin "3") (pinfunction "S_3") (pintype "passive"))
      (node (ref "R10") (pin "2") (pinfunction "2_2") (pintype "passive"))
      (node (ref "R25") (pin "2") (pinfunction "2_2") (pintype "passive"))
      (node (ref "R26") (pin "2") (pinfunction "2_2") (pintype "passive"))
      (node (ref "R9") (pin "2") (pinfunction "2_2") (pintype "passive"))
      (node (ref "U1") (pin "4") (pinfunction "COM_4") (pintype "power_in"))
      (node (ref "U2") (pin "4") (pinfunction "COM_4") (pintype "power_in"))
      (node (ref "U3") (pin "4") (pinfunction "COM_4") (pintype "power_in"))
      (node (ref "U4") (pin "4") (pinfunction "COM_4") (pintype "power_in"))
    )
    (net (code "28") (name "GND1") (class "Default")
      (node (ref "C15") (pin "1") (pinfunction "1_1") (pintype "passive"))
      (node (ref "C16") (pin "1") (pinfunction "1_1") (pintype "passive"))
      (node (ref "C21") (pin "1") (pinfunction "1_1") (pintype "passive"))
      (node (ref "C22") (pin "1") (pinfunction "1_1") (pintype "passive"))
      (node (ref "C24") (pin "1") (pinfunction "1_1") (pintype "passive"))
      (node (ref "C25") (pin "1") (pinfunction "1_1") (pintype "passive"))
      (node (ref "Hall1") (pin "5") (pinfunction "GND_5") (pintype "passive"))
      (node (ref "Hall2") (pin "5") (pinfunction "GND_5") (pintype "passive"))
      (node (ref "KIT1") (pin "2") (pinfunction "GND_2") (pintype "passive"))
      (node (ref "KIT1") (pin "35") (pinfunction "GND_35") (pintype "passive"))
      (node (ref "KIT1") (pin "9") (pinfunction "GND_9") (pintype "passive"))
      (node (ref "SPI1") (pin "1") (pinfunction "1_1") (pintype "passive"))
      (node (ref "UART1") (pin "1") (pinfunction "1_1") (pintype "passive"))
    )
    (net (code "29") (name "Net-(D7-K)") (class "Default")
      (node (ref "D5") (pin "1") (pinfunction "1_1") (pintype "passive"))
      (node (ref "D7") (pin "2") (pinfunction "K_2") (pintype "passive"))
      (node (ref "Q1") (pin "1") (pinfunction "G_1") (pintype "passive"))
      (node (ref "R1") (pin "1") (pinfunction "1_1") (pintype "passive"))
      (node (ref "R3") (pin "1") (pinfunction "1_1") (pintype "passive"))
    )
    (net (code "30") (name "Net-(D8-K)") (class "Default")
      (node (ref "D6") (pin "1") (pinfunction "1_1") (pintype "passive"))
      (node (ref "D8") (pin "2") (pinfunction "K_2") (pintype "passive"))
      (node (ref "Q2") (pin "1") (pinfunction "G_1") (pintype "passive"))
      (node (ref "R2") (pin "1") (pinfunction "1_1") (pintype "passive"))
      (node (ref "R4") (pin "1") (pinfunction "1_1") (pintype "passive"))
    )
    (net (code "31") (name "Net-(D13-K)") (class "Default")
      (node (ref "D13") (pin "2") (pinfunction "K_2") (pintype "passive"))
      (node (ref "D9") (pin "1") (pinfunction "1_1") (pintype "passive"))
      (node (ref "Q3") (pin "1") (pinfunction "G_1") (pintype "passive"))
      (node (ref "R7") (pin "1") (pinfunction "1_1") (pintype "passive"))
      (node (ref "R9") (pin "1") (pinfunction "1_1") (pintype "passive"))
    )
    (net (code "32") (name "Net-(D14-K)") (class "Default")
      (node (ref "D10") (pin "1") (pinfunction "1_1") (pintype "passive"))
      (node (ref "D14") (pin "2") (pinfunction "K_2") (pintype "passive"))
      (node (ref "Q4") (pin "1") (pinfunction "G_1") (pintype "passive"))
      (node (ref "R10") (pin "1") (pinfunction "1_1") (pintype "passive"))
      (node (ref "R8") (pin "1") (pinfunction "1_1") (pintype "passive"))
    )
    (net (code "33") (name "Net-(D21-K)") (class "Default")
      (node (ref "D19") (pin "1") (pinfunction "1_1") (pintype "passive"))
      (node (ref "D21") (pin "2") (pinfunction "K_2") (pintype "passive"))
      (node (ref "Q5") (pin "1") (pinfunction "G_1") (pintype "passive"))
      (node (ref "R17") (pin "1") (pinfunction "1_1") (pintype "passive"))
      (node (ref "R19") (pin "1") (pinfunction "1_1") (pintype "passive"))
    )
    (net (code "34") (name "Net-(D22-K)") (class "Default")
      (node (ref "D20") (pin "1") (pinfunction "1_1") (pintype "passive"))
      (node (ref "D22") (pin "2") (pinfunction "K_2") (pintype "passive"))
      (node (ref "Q6") (pin "1") (pinfunction "G_1") (pintype "passive"))
      (node (ref "R18") (pin "1") (pinfunction "1_1") (pintype "passive"))
      (node (ref "R20") (pin "1") (pinfunction "1_1") (pintype "passive"))
    )
    (net (code "35") (name "Net-(D27-K)") (class "Default")
      (node (ref "D23") (pin "1") (pinfunction "1_1") (pintype "passive"))
      (node (ref "D27") (pin "2") (pinfunction "K_2") (pintype "passive"))
      (node (ref "Q7") (pin "1") (pinfunction "G_1") (pintype "passive"))
      (node (ref "R23") (pin "1") (pinfunction "1_1") (pintype "passive"))
      (node (ref "R25") (pin "1") (pinfunction "1_1") (pintype "passive"))
    )
    (net (code "36") (name "Net-(D28-K)") (class "Default")
      (node (ref "D24") (pin "1") (pinfunction "1_1") (pintype "passive"))
      (node (ref "D28") (pin "2") (pinfunction "K_2") (pintype "passive"))
      (node (ref "Q8") (pin "1") (pinfunction "G_1") (pintype "passive"))
      (node (ref "R24") (pin "1") (pinfunction "1_1") (pintype "passive"))
      (node (ref "R26") (pin "1") (pinfunction "1_1") (pintype "passive"))
    )
    (net (code "37") (name "Net-(Hall1-FILTER)") (class "Default")
      (node (ref "C15") (pin "2") (pinfunction "2_2") (pintype "passive"))
      (node (ref "Hall1") (pin "6") (pinfunction "FILTER_6") (pintype "passive"))
    )
    (net (code "38") (name "Net-(Hall2-FILTER)") (class "Default")
      (node (ref "C21") (pin "2") (pinfunction "2_2") (pintype "passive"))
      (node (ref "Hall2") (pin "6") (pinfunction "FILTER_6") (pintype "passive"))
    )
    (net (code "39") (name "Net-(OP1-A)") (class "Default")
      (node (ref "OP1") (pin "2") (pinfunction "A_2") (pintype "passive"))
      (node (ref "R15") (pin "1") (pinfunction "1_1") (pintype "passive"))
    )
    (net (code "40") (name "Net-(OP2-A)") (class "Default")
      (node (ref "OP2") (pin "2") (pinfunction "A_2") (pintype "passive"))
      (node (ref "R16") (pin "1") (pinfunction "1_1") (pintype "passive"))
    )
    (net (code "41") (name "Net-(OP3-A)") (class "Default")
      (node (ref "OP3") (pin "2") (pinfunction "A_2") (pintype "passive"))
      (node (ref "R31") (pin "1") (pinfunction "1_1") (pintype "passive"))
    )
    (net (code "42") (name "Net-(OP4-A)") (class "Default")
      (node (ref "OP4") (pin "2") (pinfunction "A_2") (pintype "passive"))
      (node (ref "R32") (pin "1") (pinfunction "1_1") (pintype "passive"))
    )
    (net (code "43") (name "Net-(U1-HO)") (class "Default")
      (node (ref "D5") (pin "2") (pinfunction "2_2") (pintype "passive"))
      (node (ref "R3") (pin "2") (pinfunction "2_2") (pintype "passive"))
      (node (ref "U1") (pin "7") (pinfunction "HO_7") (pintype "output"))
    )
    (net (code "44") (name "Net-(U1-LO)") (class "Default")
      (node (ref "D9") (pin "2") (pinfunction "2_2") (pintype "passive"))
      (node (ref "R7") (pin "2") (pinfunction "2_2") (pintype "passive"))
      (node (ref "U1") (pin "5") (pinfunction "LO_5") (pintype "output"))
    )
    (net (code "45") (name "Net-(U1-VB)") (class "Default")
      (node (ref "C1") (pin "1") (pinfunction "1_1") (pintype "passive"))
      (node (ref "D1") (pin "2") (pinfunction "2_2") (pintype "passive"))
      (node (ref "U1") (pin "8") (pinfunction "VB_8") (pintype "power_in"))
    )
    (net (code "46") (name "Net-(U1-~{LIN})") (class "Default")
      (node (ref "R5") (pin "1") (pinfunction "1_1") (pintype "passive"))
      (node (ref "U1") (pin "3") (pinfunction "~{LIN}_3") (pintype "input"))
    )
    (net (code "47") (name "Net-(U2-HO)") (class "Default")
      (node (ref "D6") (pin "2") (pinfunction "2_2") (pintype "passive"))
      (node (ref "R4") (pin "2") (pinfunction "2_2") (pintype "passive"))
      (node (ref "U2") (pin "7") (pinfunction "HO_7") (pintype "output"))
    )
    (net (code "48") (name "Net-(U2-LO)") (class "Default")
      (node (ref "D10") (pin "2") (pinfunction "2_2") (pintype "passive"))
      (node (ref "R8") (pin "2") (pinfunction "2_2") (pintype "passive"))
      (node (ref "U2") (pin "5") (pinfunction "LO_5") (pintype "output"))
    )
    (net (code "49") (name "Net-(U2-VB)") (class "Default")
      (node (ref "C2") (pin "1") (pinfunction "1_1") (pintype "passive"))
      (node (ref "D2") (pin "2") (pinfunction "2_2") (pintype "passive"))
      (node (ref "U2") (pin "8") (pinfunction "VB_8") (pintype "power_in"))
    )
    (net (code "50") (name "Net-(U2-~{LIN})") (class "Default")
      (node (ref "R6") (pin "1") (pinfunction "1_1") (pintype "passive"))
      (node (ref "U2") (pin "3") (pinfunction "~{LIN}_3") (pintype "input"))
    )
    (net (code "51") (name "Net-(U3-HO)") (class "Default")
      (node (ref "D19") (pin "2") (pinfunction "2_2") (pintype "passive"))
      (node (ref "R19") (pin "2") (pinfunction "2_2") (pintype "passive"))
      (node (ref "U3") (pin "7") (pinfunction "HO_7") (pintype "output"))
    )
    (net (code "52") (name "Net-(U3-LO)") (class "Default")
      (node (ref "D23") (pin "2") (pinfunction "2_2") (pintype "passive"))
      (node (ref "R23") (pin "2") (pinfunction "2_2") (pintype "passive"))
      (node (ref "U3") (pin "5") (pinfunction "LO_5") (pintype "output"))
    )
    (net (code "53") (name "Net-(U3-VB)") (class "Default")
      (node (ref "C7") (pin "1") (pinfunction "1_1") (pintype "passive"))
      (node (ref "D15") (pin "2") (pinfunction "2_2") (pintype "passive"))
      (node (ref "U3") (pin "8") (pinfunction "VB_8") (pintype "power_in"))
    )
    (net (code "54") (name "Net-(U3-~{LIN})") (class "Default")
      (node (ref "R21") (pin "1") (pinfunction "1_1") (pintype "passive"))
      (node (ref "U3") (pin "3") (pinfunction "~{LIN}_3") (pintype "input"))
    )
    (net (code "55") (name "Net-(U4-HO)") (class "Default")
      (node (ref "D20") (pin "2") (pinfunction "2_2") (pintype "passive"))
      (node (ref "R20") (pin "2") (pinfunction "2_2") (pintype "passive"))
      (node (ref "U4") (pin "7") (pinfunction "HO_7") (pintype "output"))
    )
    (net (code "56") (name "Net-(U4-LO)") (class "Default")
      (node (ref "D24") (pin "2") (pinfunction "2_2") (pintype "passive"))
      (node (ref "R24") (pin "2") (pinfunction "2_2") (pintype "passive"))
      (node (ref "U4") (pin "5") (pinfunction "LO_5") (pintype "output"))
    )
    (net (code "57") (name "Net-(U4-VB)") (class "Default")
      (node (ref "C8") (pin "1") (pinfunction "1_1") (pintype "passive"))
      (node (ref "D16") (pin "2") (pinfunction "2_2") (pintype "passive"))
      (node (ref "U4") (pin "8") (pinfunction "VB_8") (pintype "power_in"))
    )
    (net (code "58") (name "Net-(U4-~{LIN})") (class "Default")
      (node (ref "R22") (pin "1") (pinfunction "1_1") (pintype "passive"))
      (node (ref "U4") (pin "3") (pinfunction "~{LIN}_3") (pintype "input"))
    )
    (net (code "59") (name "VPP") (class "Default")
      (node (ref "C11") (pin "1") (pinfunction "+_1") (pintype "passive"))
      (node (ref "C12") (pin "1") (pinfunction "+_1") (pintype "passive"))
      (node (ref "CON1") (pin "2") (pinfunction "2_2") (pintype "passive"))
      (node (ref "Q1") (pin "2") (pinfunction "D_2") (pintype "passive"))
      (node (ref "Q2") (pin "2") (pinfunction "D_2") (pintype "passive"))
      (node (ref "Q5") (pin "2") (pinfunction "D_2") (pintype "passive"))
      (node (ref "Q6") (pin "2") (pinfunction "D_2") (pintype "passive"))
    )
    (net (code "60") (name "unconnected-(AMS1-VOUT-Pad2)") (class "Default")
      (node (ref "AMS1") (pin "2") (pinfunction "VOUT_2") (pintype "passive+no_connect"))
    )
    (net (code "61") (name "unconnected-(KIT1-BOOT0-Pad39)") (class "Default")
      (node (ref "KIT1") (pin "39") (pinfunction "BOOT0_39") (pintype "passive"))
    )
    (net (code "62") (name "unconnected-(KIT1-GND-Pad33)") (class "Default")
      (node (ref "KIT1") (pin "33") (pinfunction "GND_33") (pintype "passive"))
    )
    (net (code "63") (name "unconnected-(KIT1-GND-Pad66)") (class "Default")
      (node (ref "KIT1") (pin "66") (pinfunction "GND_66") (pintype "passive"))
    )
    (net (code "64") (name "unconnected-(KIT1-NRST-Pad10)") (class "Default")
      (node (ref "KIT1") (pin "10") (pinfunction "NRST_10") (pintype "passive"))
    )
    (net (code "65") (name "unconnected-(KIT1-PA0-Pad15)") (class "Default")
      (node (ref "KIT1") (pin "15") (pinfunction "PA0_15") (pintype "passive"))
    )
    (net (code "66") (name "unconnected-(KIT1-PA1-Pad16)") (class "Default")
      (node (ref "KIT1") (pin "16") (pinfunction "PA1_16") (pintype "passive"))
    )
    (net (code "67") (name "unconnected-(KIT1-PA3-Pad18)") (class "Default")
      (node (ref "KIT1") (pin "18") (pinfunction "PA3_18") (pintype "passive"))
    )
    (net (code "68") (name "unconnected-(KIT1-PA4-Pad21)") (class "Default")
      (node (ref "KIT1") (pin "21") (pinfunction "PA4_21") (pintype "passive"))
    )
    (net (code "69") (name "unconnected-(KIT1-PA10-Pad56)") (class "Default")
      (node (ref "KIT1") (pin "56") (pinfunction "PA10_56") (pintype "passive"))
    )
    (net (code "70") (name "unconnected-(KIT1-PA11-Pad55)") (class "Default")
      (node (ref "KIT1") (pin "55") (pinfunction "PA11_55") (pintype "passive"))
    )
    (net (code "71") (name "unconnected-(KIT1-PA12-Pad54)") (class "Default")
      (node (ref "KIT1") (pin "54") (pinfunction "PA12_54") (pintype "passive"))
    )
    (net (code "72") (name "unconnected-(KIT1-PA13-Pad53)") (class "Default")
      (node (ref "KIT1") (pin "53") (pinfunction "PA13_53") (pintype "passive"))
    )
    (net (code "73") (name "unconnected-(KIT1-PA14-Pad50)") (class "Default")
      (node (ref "KIT1") (pin "50") (pinfunction "PA14_50") (pintype "passive"))
    )
    (net (code "74") (name "unconnected-(KIT1-PA15-Pad49)") (class "Default")
      (node (ref "KIT1") (pin "49") (pinfunction "PA15_49") (pintype "passive"))
    )
    (net (code "75") (name "unconnected-(KIT1-PB0-Pad27)") (class "Default")
      (node (ref "KIT1") (pin "27") (pinfunction "PB0_27") (pintype "passive"))
    )
    (net (code "76") (name "unconnected-(KIT1-PB1-Pad28)") (class "Default")
      (node (ref "KIT1") (pin "28") (pinfunction "PB1_28") (pintype "passive"))
    )
    (net (code "77") (name "unconnected-(KIT1-PB2-Pad29)") (class "Default")
      (node (ref "KIT1") (pin "29") (pinfunction "PB2_29") (pintype "passive"))
    )
    (net (code "78") (name "unconnected-(KIT1-PB3-Pad44)") (class "Default")
      (node (ref "KIT1") (pin "44") (pinfunction "PB3_44") (pintype "passive"))
    )
    (net (code "79") (name "unconnected-(KIT1-PB8-Pad37)") (class "Default")
      (node (ref "KIT1") (pin "37") (pinfunction "PB8_37") (pintype "passive"))
    )
    (net (code "80") (name "unconnected-(KIT1-PB9-Pad36)") (class "Default")
      (node (ref "KIT1") (pin "36") (pinfunction "PB9_36") (pintype "passive"))
    )
    (net (code "81") (name "unconnected-(KIT1-PB10-Pad30)") (class "Default")
      (node (ref "KIT1") (pin "30") (pinfunction "PB10_30") (pintype "passive"))
    )
    (net (code "82") (name "unconnected-(KIT1-PB11-Pad31)") (class "Default")
      (node (ref "KIT1") (pin "31") (pinfunction "PB11_31") (pintype "passive"))
    )
    (net (code "83") (name "unconnected-(KIT1-PB12-Pad32)") (class "Default")
      (node (ref "KIT1") (pin "32") (pinfunction "PB12_32") (pintype "passive"))
    )
    (net (code "84") (name "unconnected-(KIT1-PB13-Pad65)") (class "Default")
      (node (ref "KIT1") (pin "65") (pinfunction "PB13_65") (pintype "passive"))
    )
    (net (code "85") (name "unconnected-(KIT1-PB14-Pad64)") (class "Default")
      (node (ref "KIT1") (pin "64") (pinfunction "PB14_64") (pintype "passive"))
    )
    (net (code "86") (name "unconnected-(KIT1-PB15-Pad63)") (class "Default")
      (node (ref "KIT1") (pin "63") (pinfunction "PB15_63") (pintype "passive"))
    )
    (net (code "87") (name "unconnected-(KIT1-PC2-Pad13)") (class "Default")
      (node (ref "KIT1") (pin "13") (pinfunction "PC2_13") (pintype "passive"))
    )
    (net (code "88") (name "unconnected-(KIT1-PC3-Pad14)") (class "Default")
      (node (ref "KIT1") (pin "14") (pinfunction "PC3_14") (pintype "passive"))
    )
    (net (code "89") (name "unconnected-(KIT1-PC4-Pad25)") (class "Default")
      (node (ref "KIT1") (pin "25") (pinfunction "PC4_25") (pintype "passive"))
    )
    (net (code "90") (name "unconnected-(KIT1-PC5-Pad26)") (class "Default")
      (node (ref "KIT1") (pin "26") (pinfunction "PC5_26") (pintype "passive"))
    )
    (net (code "91") (name "unconnected-(KIT1-PC6-Pad62)") (class "Default")
      (node (ref "KIT1") (pin "62") (pinfunction "PC6_62") (pintype "passive"))
    )
    (net (code "92") (name "unconnected-(KIT1-PC7-Pad61)") (class "Default")
      (node (ref "KIT1") (pin "61") (pinfunction "PC7_61") (pintype "passive"))
    )
    (net (code "93") (name "unconnected-(KIT1-PC8-Pad60)") (class "Default")
      (node (ref "KIT1") (pin "60") (pinfunction "PC8_60") (pintype "passive"))
    )
    (net (code "94") (name "unconnected-(KIT1-PC9-Pad59)") (class "Default")
      (node (ref "KIT1") (pin "59") (pinfunction "PC9_59") (pintype "passive"))
    )
    (net (code "95") (name "unconnected-(KIT1-PC10-Pad48)") (class "Default")
      (node (ref "KIT1") (pin "48") (pinfunction "PC10_48") (pintype "passive"))
    )
    (net (code "96") (name "unconnected-(KIT1-PC11-Pad47)") (class "Default")
      (node (ref "KIT1") (pin "47") (pinfunction "PC11_47") (pintype "passive"))
    )
    (net (code "97") (name "unconnected-(KIT1-PC12-Pad46)") (class "Default")
      (node (ref "KIT1") (pin "46") (pinfunction "PC12_46") (pintype "passive"))
    )
    (net (code "98") (name "unconnected-(KIT1-PC13-Pad4)") (class "Default")
      (node (ref "KIT1") (pin "4") (pinfunction "PC13_4") (pintype "passive"))
    )
    (net (code "99") (name "unconnected-(KIT1-PC14-Pad5)") (class "Default")
      (node (ref "KIT1") (pin "5") (pinfunction "PC14_5") (pintype "passive"))
    )
    (net (code "100") (name "unconnected-(KIT1-PC15-Pad6)") (class "Default")
      (node (ref "KIT1") (pin "6") (pinfunction "PC15_6") (pintype "passive"))
    )
    (net (code "101") (name "unconnected-(KIT1-PD2-Pad45)") (class "Default")
      (node (ref "KIT1") (pin "45") (pinfunction "PD2_45") (pintype "passive"))
    )
    (net (code "102") (name "unconnected-(KIT1-PF0-Pad7)") (class "Default")
      (node (ref "KIT1") (pin "7") (pinfunction "PF0_7") (pintype "passive"))
    )
    (net (code "103") (name "unconnected-(KIT1-PF1-Pad8)") (class "Default")
      (node (ref "KIT1") (pin "8") (pinfunction "PF1_8") (pintype "passive"))
    )
    (net (code "104") (name "unconnected-(KIT1-PF4-Pad19)") (class "Default")
      (node (ref "KIT1") (pin "19") (pinfunction "PF4_19") (pintype "passive"))
    )
    (net (code "105") (name "unconnected-(KIT1-PF5-Pad20)") (class "Default")
      (node (ref "KIT1") (pin "20") (pinfunction "PF5_20") (pintype "passive"))
    )
    (net (code "106") (name "unconnected-(KIT1-PF6-Pad52)") (class "Default")
      (node (ref "KIT1") (pin "52") (pinfunction "PF6_52") (pintype "passive"))
    )
    (net (code "107") (name "unconnected-(KIT1-PF7-Pad51)") (class "Default")
      (node (ref "KIT1") (pin "51") (pinfunction "PF7_51") (pintype "passive"))
    )
    (net (code "108") (name "unconnected-(KIT1-VBAT-Pad3)") (class "Default")
      (node (ref "KIT1") (pin "3") (pinfunction "VBAT_3") (pintype "passive"))
    )
    (net (code "109") (name "unconnected-(KIT1-VDD-Pad38)") (class "Default")
      (node (ref "KIT1") (pin "38") (pinfunction "VDD_38") (pintype "passive"))
    )
    (net (code "110") (name "unconnected-(OP1-N{slash}C-Pad1)") (class "Default")
      (node (ref "OP1") (pin "1") (pinfunction "N/C_1") (pintype "passive"))
    )
    (net (code "111") (name "unconnected-(OP1-N{slash}C-Pad4)") (class "Default")
      (node (ref "OP1") (pin "4") (pinfunction "N/C_4") (pintype "passive"))
    )
    (net (code "112") (name "unconnected-(OP2-N{slash}C-Pad1)") (class "Default")
      (node (ref "OP2") (pin "1") (pinfunction "N/C_1") (pintype "passive"))
    )
    (net (code "113") (name "unconnected-(OP2-N{slash}C-Pad4)") (class "Default")
      (node (ref "OP2") (pin "4") (pinfunction "N/C_4") (pintype "passive"))
    )
    (net (code "114") (name "unconnected-(OP3-N{slash}C-Pad1)") (class "Default")
      (node (ref "OP3") (pin "1") (pinfunction "N/C_1") (pintype "passive"))
    )
    (net (code "115") (name "unconnected-(OP3-N{slash}C-Pad4)") (class "Default")
      (node (ref "OP3") (pin "4") (pinfunction "N/C_4") (pintype "passive"))
    )
    (net (code "116") (name "unconnected-(OP4-N{slash}C-Pad1)") (class "Default")
      (node (ref "OP4") (pin "1") (pinfunction "N/C_1") (pintype "passive"))
    )
    (net (code "117") (name "unconnected-(OP4-N{slash}C-Pad4)") (class "Default")
      (node (ref "OP4") (pin "4") (pinfunction "N/C_4") (pintype "passive"))
    )
  )
)
